# Tubes4-6.net
KiCad netlist of a schematic drawn in Altium Designer
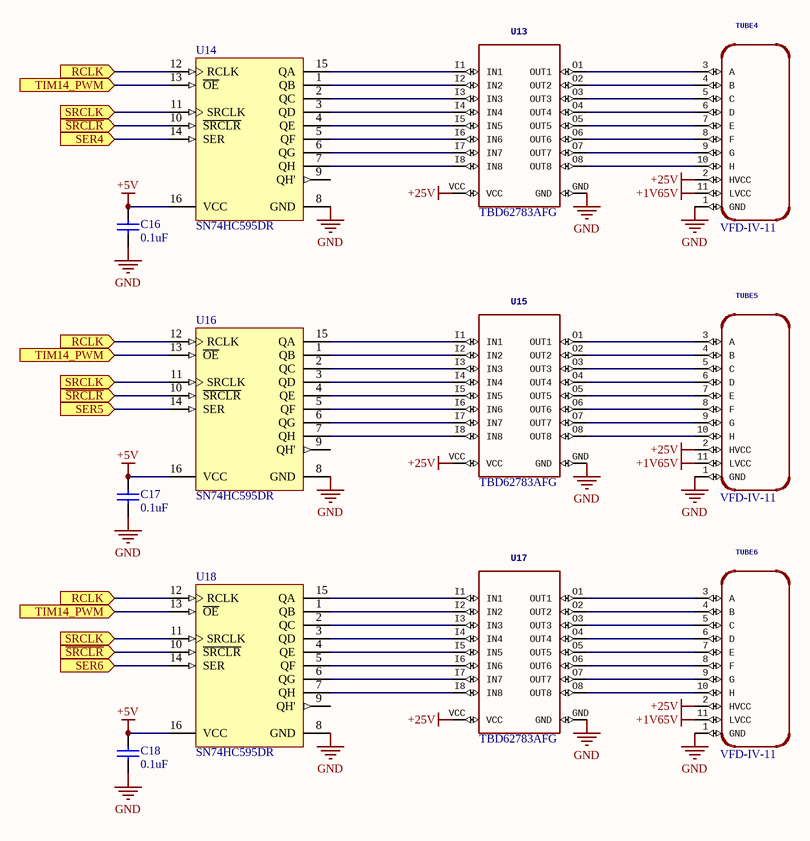
[diagram p0: Tubes4-6.SchDoc]

(export (version "E")
  (design (tool "Eeschema 10.0.6"))
  (components
    (comp (ref "C16")
      (value "0.1uF")
      (footprint "CAPC1608X90X40ML10T20")
      (fields (field (name "TOLERANCE") "±10%") (field (name "MANUFACTURER") "Yageo"))
      (libsource (lib "Altium Content Vault") (part "CAP-NP-2"))
    )
    (comp (ref "C17")
      (value "0.1uF")
      (footprint "CAPC1608X90X40ML10T20")
      (fields (field (name "TOLERANCE") "±10%") (field (name "MANUFACTURER") "Yageo"))
      (libsource (lib "Altium Content Vault") (part "CAP-NP-2"))
    )
    (comp (ref "C18")
      (value "0.1uF")
      (footprint "CAPC1608X90X40ML10T20")
      (fields (field (name "TOLERANCE") "±10%") (field (name "MANUFACTURER") "Yageo"))
      (libsource (lib "Altium Content Vault") (part "CAP-NP-2"))
    )
    (comp (ref "TUBE4")
      (value "VFD-IV-11")
      (footprint "VFD-IV11")
      (libsource (lib "VFD-Clock") (part "VFD-IV-11"))
    )
    (comp (ref "TUBE5")
      (value "VFD-IV-11")
      (footprint "VFD-IV11")
      (libsource (lib "VFD-Clock") (part "VFD-IV-11"))
    )
    (comp (ref "TUBE6")
      (value "VFD-IV-11")
      (footprint "VFD-IV11")
      (libsource (lib "VFD-Clock") (part "VFD-IV-11"))
    )
    (comp (ref "U13")
      (value "TBD62783AFG")
      (footprint "TBD62783AFG")
      (description "TUBE4")
      (libsource (lib "TBD62783AFG") (part "TBD62783AFG"))
    )
    (comp (ref "U14")
      (value "SN74HC595DR")
      (footprint "D0016A_N")
      (description "8-Bit Shift Registers With 3-State Output Registers, D0016A, LARGE T&R")
      (fields
        (field (name "GENERIC PART NUMBER") "SN74HC595")
        (field (name "MANUFACTURER") "Texas Instruments")
      )
      (libsource (lib "VFD_Clock_lib") (part "CMP-0780-00037-3"))
    )
    (comp (ref "U15")
      (value "TBD62783AFG")
      (footprint "TBD62783AFG")
      (description "TUBE5")
      (libsource (lib "TBD62783AFG") (part "TBD62783AFG"))
    )
    (comp (ref "U16")
      (value "SN74HC595DR")
      (footprint "D0016A_N")
      (description "8-Bit Shift Registers With 3-State Output Registers, D0016A, LARGE T&R")
      (fields
        (field (name "GENERIC PART NUMBER") "SN74HC595")
        (field (name "MANUFACTURER") "Texas Instruments")
      )
      (libsource (lib "VFD_Clock_lib") (part "CMP-0780-00037-3"))
    )
    (comp (ref "U17")
      (value "TBD62783AFG")
      (footprint "TBD62783AFG")
      (description "TUBE6")
      (libsource (lib "TBD62783AFG") (part "TBD62783AFG"))
    )
    (comp (ref "U18")
      (value "SN74HC595DR")
      (footprint "D0016A_N")
      (description "8-Bit Shift Registers With 3-State Output Registers, D0016A, LARGE T&R")
      (fields
        (field (name "GENERIC PART NUMBER") "SN74HC595")
        (field (name "MANUFACTURER") "Texas Instruments")
      )
      (libsource (lib "VFD_Clock_lib") (part "CMP-0780-00037-3"))
    )
  )
  (nets
    (net (code "1") (name "+1V65V") (class "Default")
      (node (ref "TUBE4") (pin "11") (pinfunction "LVCC_11") (pintype "bidirectional"))
      (node (ref "TUBE5") (pin "11") (pinfunction "LVCC_11") (pintype "bidirectional"))
      (node (ref "TUBE6") (pin "11") (pinfunction "LVCC_11") (pintype "bidirectional"))
    )
    (net (code "2") (name "+5V") (class "Default")
      (node (ref "C16") (pin "2") (pinfunction "2_2") (pintype "passive"))
      (node (ref "C17") (pin "2") (pinfunction "2_2") (pintype "passive"))
      (node (ref "C18") (pin "2") (pinfunction "2_2") (pintype "passive"))
      (node (ref "U14") (pin "16") (pinfunction "VCC_16") (pintype "power_in"))
      (node (ref "U16") (pin "16") (pinfunction "VCC_16") (pintype "power_in"))
      (node (ref "U18") (pin "16") (pinfunction "VCC_16") (pintype "power_in"))
    )
    (net (code "3") (name "+25V") (class "Default")
      (node (ref "TUBE4") (pin "2") (pinfunction "HVCC_2") (pintype "bidirectional"))
      (node (ref "TUBE5") (pin "2") (pinfunction "HVCC_2") (pintype "bidirectional"))
      (node (ref "TUBE6") (pin "2") (pinfunction "HVCC_2") (pintype "bidirectional"))
      (node (ref "U13") (pin "VCC") (pinfunction "VCC_VCC") (pintype "bidirectional"))
      (node (ref "U15") (pin "VCC") (pinfunction "VCC_VCC") (pintype "bidirectional"))
      (node (ref "U17") (pin "VCC") (pinfunction "VCC_VCC") (pintype "bidirectional"))
    )
    (net (code "4") (name "/RCLK") (class "Default")
      (node (ref "U14") (pin "12") (pinfunction "RCLK_12") (pintype "input"))
      (node (ref "U16") (pin "12") (pinfunction "RCLK_12") (pintype "input"))
      (node (ref "U18") (pin "12") (pinfunction "RCLK_12") (pintype "input"))
    )
    (net (code "5") (name "/SER4") (class "Default")
      (node (ref "U14") (pin "14") (pinfunction "SER_14") (pintype "input"))
    )
    (net (code "6") (name "/SER5") (class "Default")
      (node (ref "U16") (pin "14") (pinfunction "SER_14") (pintype "input"))
    )
    (net (code "7") (name "/SER6") (class "Default")
      (node (ref "U18") (pin "14") (pinfunction "SER_14") (pintype "input"))
    )
    (net (code "8") (name "/SRCLK") (class "Default")
      (node (ref "U14") (pin "11") (pinfunction "SRCLK_11") (pintype "input"))
      (node (ref "U16") (pin "11") (pinfunction "SRCLK_11") (pintype "input"))
      (node (ref "U18") (pin "11") (pinfunction "SRCLK_11") (pintype "input"))
    )
    (net (code "9") (name "/SRCLR") (class "Default")
      (node (ref "U14") (pin "10") (pinfunction "~{SRCLR}_10") (pintype "input"))
      (node (ref "U16") (pin "10") (pinfunction "~{SRCLR}_10") (pintype "input"))
      (node (ref "U18") (pin "10") (pinfunction "~{SRCLR}_10") (pintype "input"))
    )
    (net (code "10") (name "/TIM14_PWM") (class "Default")
      (node (ref "U14") (pin "13") (pinfunction "~{OE}_13") (pintype "input"))
      (node (ref "U16") (pin "13") (pinfunction "~{OE}_13") (pintype "input"))
      (node (ref "U18") (pin "13") (pinfunction "~{OE}_13") (pintype "input"))
    )
    (net (code "11") (name "GND") (class "Default")
      (node (ref "C16") (pin "1") (pinfunction "1_1") (pintype "passive"))
      (node (ref "C17") (pin "1") (pinfunction "1_1") (pintype "passive"))
      (node (ref "C18") (pin "1") (pinfunction "1_1") (pintype "passive"))
      (node (ref "TUBE4") (pin "1") (pinfunction "GND_1") (pintype "bidirectional"))
      (node (ref "TUBE5") (pin "1") (pinfunction "GND_1") (pintype "bidirectional"))
      (node (ref "TUBE6") (pin "1") (pinfunction "GND_1") (pintype "bidirectional"))
      (node (ref "U13") (pin "GND") (pinfunction "GND_GND") (pintype "bidirectional"))
      (node (ref "U14") (pin "8") (pinfunction "GND_8") (pintype "power_in"))
      (node (ref "U15") (pin "GND") (pinfunction "GND_GND") (pintype "bidirectional"))
      (node (ref "U16") (pin "8") (pinfunction "GND_8") (pintype "power_in"))
      (node (ref "U17") (pin "GND") (pinfunction "GND_GND") (pintype "bidirectional"))
      (node (ref "U18") (pin "8") (pinfunction "GND_8") (pintype "power_in"))
    )
    (net (code "12") (name "Net-(TUBE4-A)") (class "Default")
      (node (ref "TUBE4") (pin "3") (pinfunction "A_3") (pintype "bidirectional"))
      (node (ref "U13") (pin "O1") (pinfunction "OUT1_O1") (pintype "bidirectional"))
    )
    (net (code "13") (name "Net-(TUBE4-B)") (class "Default")
      (node (ref "TUBE4") (pin "4") (pinfunction "B_4") (pintype "bidirectional"))
      (node (ref "U13") (pin "O2") (pinfunction "OUT2_O2") (pintype "bidirectional"))
    )
    (net (code "14") (name "Net-(TUBE4-C)") (class "Default")
      (node (ref "TUBE4") (pin "5") (pinfunction "C_5") (pintype "bidirectional"))
      (node (ref "U13") (pin "O3") (pinfunction "OUT3_O3") (pintype "bidirectional"))
    )
    (net (code "15") (name "Net-(TUBE4-D)") (class "Default")
      (node (ref "TUBE4") (pin "6") (pinfunction "D_6") (pintype "bidirectional"))
      (node (ref "U13") (pin "O4") (pinfunction "OUT4_O4") (pintype "bidirectional"))
    )
    (net (code "16") (name "Net-(TUBE4-E)") (class "Default")
      (node (ref "TUBE4") (pin "7") (pinfunction "E_7") (pintype "bidirectional"))
      (node (ref "U13") (pin "O5") (pinfunction "OUT5_O5") (pintype "bidirectional"))
    )
    (net (code "17") (name "Net-(TUBE4-F)") (class "Default")
      (node (ref "TUBE4") (pin "8") (pinfunction "F_8") (pintype "bidirectional"))
      (node (ref "U13") (pin "O6") (pinfunction "OUT6_O6") (pintype "bidirectional"))
    )
    (net (code "18") (name "Net-(TUBE4-G)") (class "Default")
      (node (ref "TUBE4") (pin "9") (pinfunction "G_9") (pintype "bidirectional"))
      (node (ref "U13") (pin "O7") (pinfunction "OUT7_O7") (pintype "bidirectional"))
    )
    (net (code "19") (name "Net-(TUBE4-H)") (class "Default")
      (node (ref "TUBE4") (pin "10") (pinfunction "H_10") (pintype "bidirectional"))
      (node (ref "U13") (pin "O8") (pinfunction "OUT8_O8") (pintype "bidirectional"))
    )
    (net (code "20") (name "Net-(TUBE5-A)") (class "Default")
      (node (ref "TUBE5") (pin "3") (pinfunction "A_3") (pintype "bidirectional"))
      (node (ref "U15") (pin "O1") (pinfunction "OUT1_O1") (pintype "bidirectional"))
    )
    (net (code "21") (name "Net-(TUBE5-B)") (class "Default")
      (node (ref "TUBE5") (pin "4") (pinfunction "B_4") (pintype "bidirectional"))
      (node (ref "U15") (pin "O2") (pinfunction "OUT2_O2") (pintype "bidirectional"))
    )
    (net (code "22") (name "Net-(TUBE5-C)") (class "Default")
      (node (ref "TUBE5") (pin "5") (pinfunction "C_5") (pintype "bidirectional"))
      (node (ref "U15") (pin "O3") (pinfunction "OUT3_O3") (pintype "bidirectional"))
    )
    (net (code "23") (name "Net-(TUBE5-D)") (class "Default")
      (node (ref "TUBE5") (pin "6") (pinfunction "D_6") (pintype "bidirectional"))
      (node (ref "U15") (pin "O4") (pinfunction "OUT4_O4") (pintype "bidirectional"))
    )
    (net (code "24") (name "Net-(TUBE5-E)") (class "Default")
      (node (ref "TUBE5") (pin "7") (pinfunction "E_7") (pintype "bidirectional"))
      (node (ref "U15") (pin "O5") (pinfunction "OUT5_O5") (pintype "bidirectional"))
    )
    (net (code "25") (name "Net-(TUBE5-F)") (class "Default")
      (node (ref "TUBE5") (pin "8") (pinfunction "F_8") (pintype "bidirectional"))
      (node (ref "U15") (pin "O6") (pinfunction "OUT6_O6") (pintype "bidirectional"))
    )
    (net (code "26") (name "Net-(TUBE5-G)") (class "Default")
      (node (ref "TUBE5") (pin "9") (pinfunction "G_9") (pintype "bidirectional"))
      (node (ref "U15") (pin "O7") (pinfunction "OUT7_O7") (pintype "bidirectional"))
    )
    (net (code "27") (name "Net-(TUBE5-H)") (class "Default")
      (node (ref "TUBE5") (pin "10") (pinfunction "H_10") (pintype "bidirectional"))
      (node (ref "U15") (pin "O8") (pinfunction "OUT8_O8") (pintype "bidirectional"))
    )
    (net (code "28") (name "Net-(TUBE6-A)") (class "Default")
      (node (ref "TUBE6") (pin "3") (pinfunction "A_3") (pintype "bidirectional"))
      (node (ref "U17") (pin "O1") (pinfunction "OUT1_O1") (pintype "bidirectional"))
    )
    (net (code "29") (name "Net-(TUBE6-B)") (class "Default")
      (node (ref "TUBE6") (pin "4") (pinfunction "B_4") (pintype "bidirectional"))
      (node (ref "U17") (pin "O2") (pinfunction "OUT2_O2") (pintype "bidirectional"))
    )
    (net (code "30") (name "Net-(TUBE6-C)") (class "Default")
      (node (ref "TUBE6") (pin "5") (pinfunction "C_5") (pintype "bidirectional"))
      (node (ref "U17") (pin "O3") (pinfunction "OUT3_O3") (pintype "bidirectional"))
    )
    (net (code "31") (name "Net-(TUBE6-D)") (class "Default")
      (node (ref "TUBE6") (pin "6") (pinfunction "D_6") (pintype "bidirectional"))
      (node (ref "U17") (pin "O4") (pinfunction "OUT4_O4") (pintype "bidirectional"))
    )
    (net (code "32") (name "Net-(TUBE6-E)") (class "Default")
      (node (ref "TUBE6") (pin "7") (pinfunction "E_7") (pintype "bidirectional"))
      (node (ref "U17") (pin "O5") (pinfunction "OUT5_O5") (pintype "bidirectional"))
    )
    (net (code "33") (name "Net-(TUBE6-F)") (class "Default")
      (node (ref "TUBE6") (pin "8") (pinfunction "F_8") (pintype "bidirectional"))
      (node (ref "U17") (pin "O6") (pinfunction "OUT6_O6") (pintype "bidirectional"))
    )
    (net (code "34") (name "Net-(TUBE6-G)") (class "Default")
      (node (ref "TUBE6") (pin "9") (pinfunction "G_9") (pintype "bidirectional"))
      (node (ref "U17") (pin "O7") (pinfunction "OUT7_O7") (pintype "bidirectional"))
    )
    (net (code "35") (name "Net-(TUBE6-H)") (class "Default")
      (node (ref "TUBE6") (pin "10") (pinfunction "H_10") (pintype "bidirectional"))
      (node (ref "U17") (pin "O8") (pinfunction "OUT8_O8") (pintype "bidirectional"))
    )
    (net (code "36") (name "Net-(U13-IN1)") (class "Default")
      (node (ref "U13") (pin "I1") (pinfunction "IN1_I1") (pintype "bidirectional"))
      (node (ref "U14") (pin "15") (pinfunction "QA_15") (pintype "tri_state"))
    )
    (net (code "37") (name "Net-(U13-IN2)") (class "Default")
      (node (ref "U13") (pin "I2") (pinfunction "IN2_I2") (pintype "bidirectional"))
      (node (ref "U14") (pin "1") (pinfunction "QB_1") (pintype "tri_state"))
    )
    (net (code "38") (name "Net-(U13-IN3)") (class "Default")
      (node (ref "U13") (pin "I3") (pinfunction "IN3_I3") (pintype "bidirectional"))
      (node (ref "U14") (pin "2") (pinfunction "QC_2") (pintype "tri_state"))
    )
    (net (code "39") (name "Net-(U13-IN4)") (class "Default")
      (node (ref "U13") (pin "I4") (pinfunction "IN4_I4") (pintype "bidirectional"))
      (node (ref "U14") (pin "3") (pinfunction "QD_3") (pintype "tri_state"))
    )
    (net (code "40") (name "Net-(U13-IN5)") (class "Default")
      (node (ref "U13") (pin "I5") (pinfunction "IN5_I5") (pintype "bidirectional"))
      (node (ref "U14") (pin "4") (pinfunction "QE_4") (pintype "tri_state"))
    )
    (net (code "41") (name "Net-(U13-IN6)") (class "Default")
      (node (ref "U13") (pin "I6") (pinfunction "IN6_I6") (pintype "bidirectional"))
      (node (ref "U14") (pin "5") (pinfunction "QF_5") (pintype "tri_state"))
    )
    (net (code "42") (name "Net-(U13-IN7)") (class "Default")
      (node (ref "U13") (pin "I7") (pinfunction "IN7_I7") (pintype "bidirectional"))
      (node (ref "U14") (pin "6") (pinfunction "QG_6") (pintype "tri_state"))
    )
    (net (code "43") (name "Net-(U13-IN8)") (class "Default")
      (node (ref "U13") (pin "I8") (pinfunction "IN8_I8") (pintype "bidirectional"))
      (node (ref "U14") (pin "7") (pinfunction "QH_7") (pintype "tri_state"))
    )
    (net (code "44") (name "Net-(U15-IN1)") (class "Default")
      (node (ref "U15") (pin "I1") (pinfunction "IN1_I1") (pintype "bidirectional"))
      (node (ref "U16") (pin "15") (pinfunction "QA_15") (pintype "tri_state"))
    )
    (net (code "45") (name "Net-(U15-IN2)") (class "Default")
      (node (ref "U15") (pin "I2") (pinfunction "IN2_I2") (pintype "bidirectional"))
      (node (ref "U16") (pin "1") (pinfunction "QB_1") (pintype "tri_state"))
    )
    (net (code "46") (name "Net-(U15-IN3)") (class "Default")
      (node (ref "U15") (pin "I3") (pinfunction "IN3_I3") (pintype "bidirectional"))
      (node (ref "U16") (pin "2") (pinfunction "QC_2") (pintype "tri_state"))
    )
    (net (code "47") (name "Net-(U15-IN4)") (class "Default")
      (node (ref "U15") (pin "I4") (pinfunction "IN4_I4") (pintype "bidirectional"))
      (node (ref "U16") (pin "3") (pinfunction "QD_3") (pintype "tri_state"))
    )
    (net (code "48") (name "Net-(U15-IN5)") (class "Default")
      (node (ref "U15") (pin "I5") (pinfunction "IN5_I5") (pintype "bidirectional"))
      (node (ref "U16") (pin "4") (pinfunction "QE_4") (pintype "tri_state"))
    )
    (net (code "49") (name "Net-(U15-IN6)") (class "Default")
      (node (ref "U15") (pin "I6") (pinfunction "IN6_I6") (pintype "bidirectional"))
      (node (ref "U16") (pin "5") (pinfunction "QF_5") (pintype "tri_state"))
    )
    (net (code "50") (name "Net-(U15-IN7)") (class "Default")
      (node (ref "U15") (pin "I7") (pinfunction "IN7_I7") (pintype "bidirectional"))
      (node (ref "U16") (pin "6") (pinfunction "QG_6") (pintype "tri_state"))
    )
    (net (code "51") (name "Net-(U15-IN8)") (class "Default")
      (node (ref "U15") (pin "I8") (pinfunction "IN8_I8") (pintype "bidirectional"))
      (node (ref "U16") (pin "7") (pinfunction "QH_7") (pintype "tri_state"))
    )
    (net (code "52") (name "Net-(U17-IN1)") (class "Default")
      (node (ref "U17") (pin "I1") (pinfunction "IN1_I1") (pintype "bidirectional"))
      (node (ref "U18") (pin "15") (pinfunction "QA_15") (pintype "tri_state"))
    )
    (net (code "53") (name "Net-(U17-IN2)") (class "Default")
      (node (ref "U17") (pin "I2") (pinfunction "IN2_I2") (pintype "bidirectional"))
      (node (ref "U18") (pin "1") (pinfunction "QB_1") (pintype "tri_state"))
    )
    (net (code "54") (name "Net-(U17-IN3)") (class "Default")
      (node (ref "U17") (pin "I3") (pinfunction "IN3_I3") (pintype "bidirectional"))
      (node (ref "U18") (pin "2") (pinfunction "QC_2") (pintype "tri_state"))
    )
    (net (code "55") (name "Net-(U17-IN4)") (class "Default")
      (node (ref "U17") (pin "I4") (pinfunction "IN4_I4") (pintype "bidirectional"))
      (node (ref "U18") (pin "3") (pinfunction "QD_3") (pintype "tri_state"))
    )
    (net (code "56") (name "Net-(U17-IN5)") (class "Default")
      (node (ref "U17") (pin "I5") (pinfunction "IN5_I5") (pintype "bidirectional"))
      (node (ref "U18") (pin "4") (pinfunction "QE_4") (pintype "tri_state"))
    )
    (net (code "57") (name "Net-(U17-IN6)") (class "Default")
      (node (ref "U17") (pin "I6") (pinfunction "IN6_I6") (pintype "bidirectional"))
      (node (ref "U18") (pin "5") (pinfunction "QF_5") (pintype "tri_state"))
    )
    (net (code "58") (name "Net-(U17-IN7)") (class "Default")
      (node (ref "U17") (pin "I7") (pinfunction "IN7_I7") (pintype "bidirectional"))
      (node (ref "U18") (pin "6") (pinfunction "QG_6") (pintype "tri_state"))
    )
    (net (code "59") (name "Net-(U17-IN8)") (class "Default")
      (node (ref "U17") (pin "I8") (pinfunction "IN8_I8") (pintype "bidirectional"))
      (node (ref "U18") (pin "7") (pinfunction "QH_7") (pintype "tri_state"))
    )
    (net (code "60") (name "unconnected-(U14-QH'-Pad9)") (class "Default")
      (node (ref "U14") (pin "9") (pinfunction "QH'_9") (pintype "output"))
    )
    (net (code "61") (name "unconnected-(U16-QH'-Pad9)") (class "Default")
      (node (ref "U16") (pin "9") (pinfunction "QH'_9") (pintype "output"))
    )
    (net (code "62") (name "unconnected-(U18-QH'-Pad9)") (class "Default")
      (node (ref "U18") (pin "9") (pinfunction "QH'_9") (pintype "output"))
    )
  )
)
